# IB_V2_AUDIO.net
KiCad netlist of a schematic drawn in Altium Designer
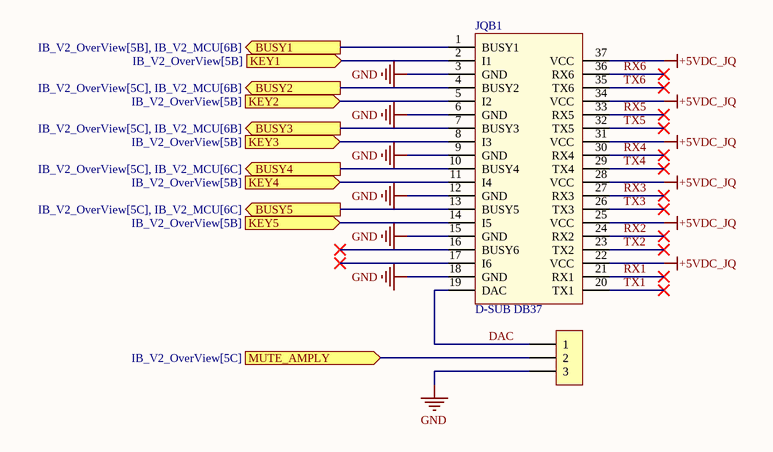
[diagram p0: IB_V2_AUDIO.SchDoc]

(export (version "E")
  (design (tool "Eeschema 10.0.6"))
  (components
    (comp (ref "H6")
      (value "Header 3P 2.54 Duc Thang")
      (footprint "XH2.54M-3")
      (description "Cắm")
      (libsource (lib "Header") (part "Header 3P 2.54 Duc Thang"))
    )
    (comp (ref "JQB1")
      (value "D-SUB DB37")
      (footprint "JQ BOARD")
      (description "DB37-2.77 Cái Thẳng 2 Hàng chân hàn PCB")
      (libsource (lib "SCH_LIB") (part "JQ8900"))
    )
  )
  (nets
    (net (code "1") (name "+5VDC_JQ") (class "Default")
      (node (ref "JQB1") (pin "22") (pinfunction "VCC_22") (pintype "passive"))
      (node (ref "JQB1") (pin "25") (pinfunction "VCC_25") (pintype "passive"))
      (node (ref "JQB1") (pin "28") (pinfunction "VCC_28") (pintype "passive"))
      (node (ref "JQB1") (pin "31") (pinfunction "VCC_31") (pintype "passive"))
      (node (ref "JQB1") (pin "34") (pinfunction "VCC_34") (pintype "passive"))
      (node (ref "JQB1") (pin "37") (pinfunction "VCC_37") (pintype "passive"))
    )
    (net (code "2") (name "/BUSY1") (class "Default")
      (node (ref "JQB1") (pin "1") (pinfunction "BUSY1_1") (pintype "passive"))
    )
    (net (code "3") (name "/BUSY2") (class "Default")
      (node (ref "JQB1") (pin "4") (pinfunction "BUSY2_4") (pintype "passive"))
    )
    (net (code "4") (name "/BUSY3") (class "Default")
      (node (ref "JQB1") (pin "7") (pinfunction "BUSY3_7") (pintype "passive"))
    )
    (net (code "5") (name "/BUSY4") (class "Default")
      (node (ref "JQB1") (pin "10") (pinfunction "BUSY4_10") (pintype "passive"))
    )
    (net (code "6") (name "/BUSY5") (class "Default")
      (node (ref "JQB1") (pin "13") (pinfunction "BUSY5_13") (pintype "passive"))
    )
    (net (code "7") (name "/DAC") (class "Default")
      (node (ref "H6") (pin "1") (pinfunction "1_1") (pintype "passive"))
      (node (ref "JQB1") (pin "19") (pinfunction "DAC_19") (pintype "passive"))
    )
    (net (code "8") (name "/KEY1") (class "Default")
      (node (ref "JQB1") (pin "2") (pinfunction "I1_2") (pintype "passive"))
    )
    (net (code "9") (name "/KEY2") (class "Default")
      (node (ref "JQB1") (pin "5") (pinfunction "I2_5") (pintype "passive"))
    )
    (net (code "10") (name "/KEY3") (class "Default")
      (node (ref "JQB1") (pin "8") (pinfunction "I3_8") (pintype "passive"))
    )
    (net (code "11") (name "/KEY4") (class "Default")
      (node (ref "JQB1") (pin "11") (pinfunction "I4_11") (pintype "passive"))
    )
    (net (code "12") (name "/KEY5") (class "Default")
      (node (ref "JQB1") (pin "14") (pinfunction "I5_14") (pintype "passive"))
    )
    (net (code "13") (name "/MUTE_AMPLY") (class "Default")
      (node (ref "H6") (pin "2") (pinfunction "2_2") (pintype "passive"))
    )
    (net (code "14") (name "/RX1") (class "Default")
      (node (ref "JQB1") (pin "21") (pinfunction "RX1_21") (pintype "passive+no_connect"))
    )
    (net (code "15") (name "/RX2") (class "Default")
      (node (ref "JQB1") (pin "24") (pinfunction "RX2_24") (pintype "passive+no_connect"))
    )
    (net (code "16") (name "/RX3") (class "Default")
      (node (ref "JQB1") (pin "27") (pinfunction "RX3_27") (pintype "passive+no_connect"))
    )
    (net (code "17") (name "/RX4") (class "Default")
      (node (ref "JQB1") (pin "30") (pinfunction "RX4_30") (pintype "passive+no_connect"))
    )
    (net (code "18") (name "/RX5") (class "Default")
      (node (ref "JQB1") (pin "33") (pinfunction "RX5_33") (pintype "passive+no_connect"))
    )
    (net (code "19") (name "/RX6") (class "Default")
      (node (ref "JQB1") (pin "36") (pinfunction "RX6_36") (pintype "passive+no_connect"))
    )
    (net (code "20") (name "/TX1") (class "Default")
      (node (ref "JQB1") (pin "20") (pinfunction "TX1_20") (pintype "passive+no_connect"))
    )
    (net (code "21") (name "/TX2") (class "Default")
      (node (ref "JQB1") (pin "23") (pinfunction "TX2_23") (pintype "passive+no_connect"))
    )
    (net (code "22") (name "/TX3") (class "Default")
      (node (ref "JQB1") (pin "26") (pinfunction "TX3_26") (pintype "passive+no_connect"))
    )
    (net (code "23") (name "/TX4") (class "Default")
      (node (ref "JQB1") (pin "29") (pinfunction "TX4_29") (pintype "passive+no_connect"))
    )
    (net (code "24") (name "/TX5") (class "Default")
      (node (ref "JQB1") (pin "32") (pinfunction "TX5_32") (pintype "passive+no_connect"))
    )
    (net (code "25") (name "/TX6") (class "Default")
      (node (ref "JQB1") (pin "35") (pinfunction "TX6_35") (pintype "passive+no_connect"))
    )
    (net (code "26") (name "GND") (class "Default")
      (node (ref "H6") (pin "3") (pinfunction "3_3") (pintype "passive"))
      (node (ref "JQB1") (pin "12") (pinfunction "GND_12") (pintype "passive"))
      (node (ref "JQB1") (pin "15") (pinfunction "GND_15") (pintype "passive"))
      (node (ref "JQB1") (pin "18") (pinfunction "GND_18") (pintype "passive"))
      (node (ref "JQB1") (pin "3") (pinfunction "GND_3") (pintype "passive"))
      (node (ref "JQB1") (pin "6") (pinfunction "GND_6") (pintype "passive"))
      (node (ref "JQB1") (pin "9") (pinfunction "GND_9") (pintype "passive"))
    )
    (net (code "27") (name "unconnected-(JQB1-BUSY6-Pad16)") (class "Default")
      (node (ref "JQB1") (pin "16") (pinfunction "BUSY6_16") (pintype "passive+no_connect"))
    )
    (net (code "28") (name "unconnected-(JQB1-I6-Pad17)") (class "Default")
      (node (ref "JQB1") (pin "17") (pinfunction "I6_17") (pintype "passive+no_connect"))
    )
  )
)
